# Top.net
KiCad netlist of a schematic drawn in Altium Designer
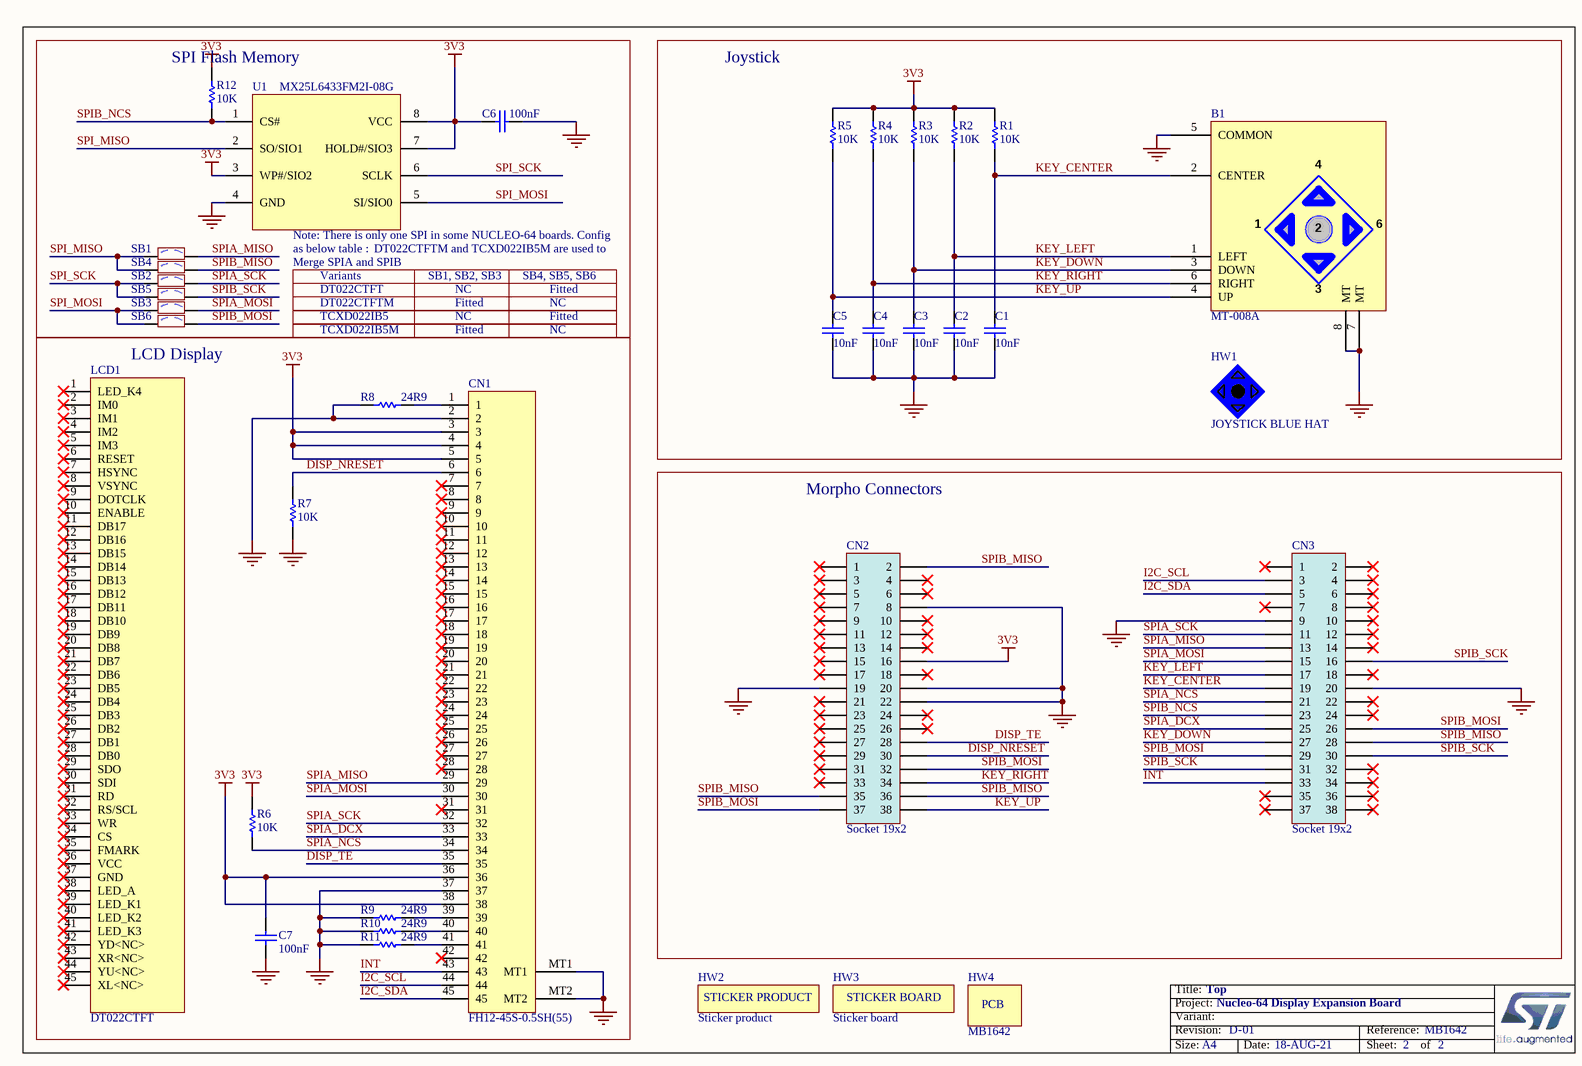
[diagram p0: Top.SchDoc]

(export (version "E")
  (design (tool "Eeschema 10.0.6"))
  (components
    (comp (ref "B1")
      (value "MT-008A")
      (footprint "SWI_XIEJIA_MT-008A_6P")
      (description "Joystick, 4 dir, 1 OK")
      (fields
        (field (name "INTERNAL_PART_NUMBER") "MCD-00132")
        (field (name "MANUFACTURER") "XIEJIA ELECTRONICS")
        (field (name "PROVIDED_BY") "SUBCO")
      )
      (libsource (lib "MCD_PARTS_database") (part "Joystick MT-008A_M"))
    )
    (comp (ref "C1")
      (value "10nF")
      (footprint "C0603")
      (description "Capacitor,10nF,100V,X7R,10%,0603")
      (fields
        (field (name "INTERNAL_PART_NUMBER") "MCD-01098")
        (field (name "MANUFACTURER_PART_NUMBER") "CC0603KRX7R0BB103")
        (field (name "PROVIDED_BY") "SUBCO")
      )
      (libsource (lib "MCD_PARTS_database") (part "Capacitor"))
    )
    (comp (ref "C2")
      (value "10nF")
      (footprint "C0603")
      (description "Capacitor,10nF,100V,X7R,10%,0603")
      (fields
        (field (name "INTERNAL_PART_NUMBER") "MCD-01098")
        (field (name "MANUFACTURER_PART_NUMBER") "CC0603KRX7R0BB103")
        (field (name "PROVIDED_BY") "SUBCO")
      )
      (libsource (lib "MCD_PARTS_database") (part "Capacitor"))
    )
    (comp (ref "C3")
      (value "10nF")
      (footprint "C0603")
      (description "Capacitor,10nF,100V,X7R,10%,0603")
      (fields
        (field (name "INTERNAL_PART_NUMBER") "MCD-01098")
        (field (name "MANUFACTURER_PART_NUMBER") "CC0603KRX7R0BB103")
        (field (name "PROVIDED_BY") "SUBCO")
      )
      (libsource (lib "MCD_PARTS_database") (part "Capacitor"))
    )
    (comp (ref "C4")
      (value "10nF")
      (footprint "C0603")
      (description "Capacitor,10nF,100V,X7R,10%,0603")
      (fields
        (field (name "INTERNAL_PART_NUMBER") "MCD-01098")
        (field (name "MANUFACTURER_PART_NUMBER") "CC0603KRX7R0BB103")
        (field (name "PROVIDED_BY") "SUBCO")
      )
      (libsource (lib "MCD_PARTS_database") (part "Capacitor"))
    )
    (comp (ref "C5")
      (value "10nF")
      (footprint "C0603")
      (description "Capacitor,10nF,100V,X7R,10%,0603")
      (fields
        (field (name "INTERNAL_PART_NUMBER") "MCD-01098")
        (field (name "MANUFACTURER_PART_NUMBER") "CC0603KRX7R0BB103")
        (field (name "PROVIDED_BY") "SUBCO")
      )
      (libsource (lib "MCD_PARTS_database") (part "Capacitor"))
    )
    (comp (ref "C6")
      (value "100nF")
      (footprint "C0603")
      (description "Capacitor, MLCC, 100nF, 16V, X7R, +/-10%, 0603, T=0,8mm")
      (fields (field (name "INTERNAL_PART_NUMBER") "MCD-00211") (field (name "MANUFACTURER") "YAGEO"))
      (libsource (lib "MCD_PARTS_database") (part "Capacitor"))
    )
    (comp (ref "C7")
      (value "100nF")
      (footprint "C0603")
      (description "Capacitor, MLCC, 100nF, 16V, X7R, +/-10%, 0603, T=0,8mm")
      (fields (field (name "INTERNAL_PART_NUMBER") "MCD-00211") (field (name "MANUFACTURER") "YAGEO"))
      (libsource (lib "MCD_PARTS_database") (part "Capacitor"))
    )
    (comp (ref "CN1")
      (value "FH12-45S-0.5SH(55)")
      (footprint "CON_HRS_FH12-45S-05SH")
      (description "45 pins P 0.5 surface mount connector")
      (fields
        (field (name "INTERNAL_PART_NUMBER") "MCD-01980")
        (field (name "MANUFACTURER") "HIROSE")
        (field (name "PROVIDED_BY") "SUBCO")
      )
      (libsource (lib "MCD_PARTS_database") (part "FH12-45S-0.5SH(55)"))
    )
    (comp (ref "CN2")
      (value "Socket 19x2")
      (footprint "CON_SAMTEC_SSW-119-01-X-D")
      (description "Socket, 19x2, 2.54mm, VR, TH, Height 8.51mm/2.64mm")
      (fields
        (field (name "INTERNAL_PART_NUMBER") "MCD-01845")
        (field (name "MANUFACTURER_PART_NUMBER") "SSW-119-01-x-D")
        (field (name "PROVIDED_BY") "SUBCO")
      )
      (libsource (lib "MCD_PARTS_database") (part "Socket 19x2"))
    )
    (comp (ref "CN3")
      (value "Socket 19x2")
      (footprint "CON_SAMTEC_SSW-119-01-X-D")
      (description "Socket, 19x2, 2.54mm, VR, TH, Height 8.51mm/2.64mm")
      (fields
        (field (name "INTERNAL_PART_NUMBER") "MCD-01845")
        (field (name "MANUFACTURER_PART_NUMBER") "SSW-119-01-x-D")
        (field (name "PROVIDED_BY") "SUBCO")
      )
      (libsource (lib "MCD_PARTS_database") (part "Socket 19x2"))
    )
    (comp (ref "HW1")
      (value "JOYSTICK BLUE HAT")
      (description "Joystick Blue Hat")
      (fields
        (field (name "INTERNAL_PART_NUMBER") "MCD-01337")
        (field (name "MANUFACTURER_PART_NUMBER") "PB-504")
        (field (name "PROVIDED_BY") "SUBCO")
      )
      (libsource (lib "MCD_PARTS_database") (part "JOYSTICK_BLUE_HAT"))
    )
    (comp (ref "HW2")
      (value "Sticker product")
      (footprint "STICKER_PRODUCT_25X5")
      (description "Sticker product 25x5 mm")
      (fields (field (name "INTERNAL_PART_NUMBER") "MCD-02189") (field (name "Comment") "STICKER_PRODUCT"))
      (libsource (lib "MCD_PARTS_database") (part "STICKER_PRODUCT"))
    )
    (comp (ref "HW3")
      (value "Sticker board")
      (footprint "STICKER_BOARD_25X5")
      (description "Sticker board 25x5 mm")
      (fields (field (name "INTERNAL_PART_NUMBER") "MCD-02190") (field (name "Comment") "STICKER_BOARD"))
      (libsource (lib "MCD_PARTS_database") (part "STICKER_BOARD"))
    )
    (comp (ref "HW4")
      (value "MB1642")
      (description "MB1642 PCB")
      (fields (field (name "INTERNAL_PART_NUMBER") "MCD-02495") (field (name "Comment") "PCB"))
      (libsource (lib "MCD_PARTS_database") (part "PCB"))
    )
    (comp (ref "LCD1")
      (value "DT022CTFT")
      (footprint "LCD_DISPLAYTECH_DT022CTFT_45P_P050")
      (description "240x320 2.2inch display")
      (fields
        (field (name "INTERNAL_PART_NUMBER") "MCD-01982")
        (field (name "MANUFACTURER") "DISPLAYTECH")
        (field (name "PROVIDED_BY") "SUBCO")
      )
      (libsource (lib "MCD_PARTS_database") (part "DT022CTFT"))
    )
    (comp (ref "R1")
      (value "10K")
      (footprint "R0603")
      (description "Resistor,10K,0603,1%,1/10W")
      (fields
        (field (name "INTERNAL_PART_NUMBER") "MCD-00220")
        (field (name "MANUFACTURER_PART_NUMBER") "RC0603FR-0710KL")
        (field (name "PROVIDED_BY") "SUBCO")
      )
      (libsource (lib "MCD_PARTS_database") (part "Resistor"))
    )
    (comp (ref "R2")
      (value "10K")
      (footprint "R0603")
      (description "Resistor,10K,0603,1%,1/10W")
      (fields
        (field (name "INTERNAL_PART_NUMBER") "MCD-00220")
        (field (name "MANUFACTURER_PART_NUMBER") "RC0603FR-0710KL")
        (field (name "PROVIDED_BY") "SUBCO")
      )
      (libsource (lib "MCD_PARTS_database") (part "Resistor"))
    )
    (comp (ref "R3")
      (value "10K")
      (footprint "R0603")
      (description "Resistor,10K,0603,1%,1/10W")
      (fields
        (field (name "INTERNAL_PART_NUMBER") "MCD-00220")
        (field (name "MANUFACTURER_PART_NUMBER") "RC0603FR-0710KL")
        (field (name "PROVIDED_BY") "SUBCO")
      )
      (libsource (lib "MCD_PARTS_database") (part "Resistor"))
    )
    (comp (ref "R4")
      (value "10K")
      (footprint "R0603")
      (description "Resistor,10K,0603,1%,1/10W")
      (fields
        (field (name "INTERNAL_PART_NUMBER") "MCD-00220")
        (field (name "MANUFACTURER_PART_NUMBER") "RC0603FR-0710KL")
        (field (name "PROVIDED_BY") "SUBCO")
      )
      (libsource (lib "MCD_PARTS_database") (part "Resistor"))
    )
    (comp (ref "R5")
      (value "10K")
      (footprint "R0603")
      (description "Resistor,10K,0603,1%,1/10W")
      (fields
        (field (name "INTERNAL_PART_NUMBER") "MCD-00220")
        (field (name "MANUFACTURER_PART_NUMBER") "RC0603FR-0710KL")
        (field (name "PROVIDED_BY") "SUBCO")
      )
      (libsource (lib "MCD_PARTS_database") (part "Resistor"))
    )
    (comp (ref "R6")
      (value "10K")
      (footprint "R0603")
      (description "Resistor,10K,0603,1%,1/10W")
      (fields
        (field (name "INTERNAL_PART_NUMBER") "MCD-00220")
        (field (name "MANUFACTURER_PART_NUMBER") "RC0603FR-0710KL")
        (field (name "PROVIDED_BY") "SUBCO")
      )
      (libsource (lib "MCD_PARTS_database") (part "Resistor"))
    )
    (comp (ref "R7")
      (value "10K")
      (footprint "R0603")
      (description "Resistor,10K,0603,1%,1/10W")
      (fields
        (field (name "INTERNAL_PART_NUMBER") "MCD-00220")
        (field (name "MANUFACTURER_PART_NUMBER") "RC0603FR-0710KL")
        (field (name "PROVIDED_BY") "SUBCO")
      )
      (libsource (lib "MCD_PARTS_database") (part "Resistor"))
    )
    (comp (ref "R8")
      (value "24R9")
      (footprint "R1206_H0P55")
      (description "Resistor, 24R9, 1206, +/-1%, 1/4W")
      (fields
        (field (name "INTERNAL_PART_NUMBER") "MCD-02611")
        (field (name "MANUFACTURER_PART_NUMBER") "RC1206FR-0724R9L")
      )
      (libsource (lib "MCD_PARTS_database") (part "Resistor"))
    )
    (comp (ref "R9")
      (value "24R9")
      (footprint "R1206_H0P55")
      (description "Resistor, 24R9, 1206, +/-1%, 1/4W")
      (fields
        (field (name "INTERNAL_PART_NUMBER") "MCD-02611")
        (field (name "MANUFACTURER_PART_NUMBER") "RC1206FR-0724R9L")
      )
      (libsource (lib "MCD_PARTS_database") (part "Resistor"))
    )
    (comp (ref "R10")
      (value "24R9")
      (footprint "R1206_H0P55")
      (description "Resistor, 24R9, 1206, +/-1%, 1/4W")
      (fields
        (field (name "INTERNAL_PART_NUMBER") "MCD-02611")
        (field (name "MANUFACTURER_PART_NUMBER") "RC1206FR-0724R9L")
      )
      (libsource (lib "MCD_PARTS_database") (part "Resistor"))
    )
    (comp (ref "R11")
      (value "24R9")
      (footprint "R1206_H0P55")
      (description "Resistor, 24R9, 1206, +/-1%, 1/4W")
      (fields
        (field (name "INTERNAL_PART_NUMBER") "MCD-02611")
        (field (name "MANUFACTURER_PART_NUMBER") "RC1206FR-0724R9L")
      )
      (libsource (lib "MCD_PARTS_database") (part "Resistor"))
    )
    (comp (ref "R12")
      (value "10K")
      (footprint "R0603")
      (description "Resistor,10K,0603,1%,1/10W")
      (fields
        (field (name "INTERNAL_PART_NUMBER") "MCD-00220")
        (field (name "MANUFACTURER_PART_NUMBER") "RC0603FR-0710KL")
        (field (name "PROVIDED_BY") "SUBCO")
      )
      (libsource (lib "MCD_PARTS_database") (part "Resistor"))
    )
    (comp (ref "SB1")
      (value "SB_OFF")
      (footprint "SOLDER-BRIDGE_R0603-0R")
      (description "Solder Bridge OFF")
      (fields (field (name "INTERNAL_PART_NUMBER") "MCD-00072") (field (name "MANUFACTURER") "YAGEO"))
      (libsource (lib "MCD_PARTS_database") (part "SB_OFF"))
    )
    (comp (ref "SB2")
      (value "SB_OFF")
      (footprint "SOLDER-BRIDGE_R0603-0R")
      (description "Solder Bridge OFF")
      (fields (field (name "INTERNAL_PART_NUMBER") "MCD-00072") (field (name "MANUFACTURER") "YAGEO"))
      (libsource (lib "MCD_PARTS_database") (part "SB_OFF"))
    )
    (comp (ref "SB3")
      (value "SB_OFF")
      (footprint "SOLDER-BRIDGE_R0603-0R")
      (description "Solder Bridge OFF")
      (fields (field (name "INTERNAL_PART_NUMBER") "MCD-00072") (field (name "MANUFACTURER") "YAGEO"))
      (libsource (lib "MCD_PARTS_database") (part "SB_OFF"))
    )
    (comp (ref "SB4")
      (value "SB_OFF")
      (footprint "SOLDER-BRIDGE_R0603-0R")
      (description "Solder Bridge OFF")
      (fields (field (name "INTERNAL_PART_NUMBER") "MCD-00072") (field (name "MANUFACTURER") "YAGEO"))
      (libsource (lib "MCD_PARTS_database") (part "SB_OFF"))
    )
    (comp (ref "SB5")
      (value "SB_OFF")
      (footprint "SOLDER-BRIDGE_R0603-0R")
      (description "Solder Bridge OFF")
      (fields (field (name "INTERNAL_PART_NUMBER") "MCD-00072") (field (name "MANUFACTURER") "YAGEO"))
      (libsource (lib "MCD_PARTS_database") (part "SB_OFF"))
    )
    (comp (ref "SB6")
      (value "SB_OFF")
      (footprint "SOLDER-BRIDGE_R0603-0R")
      (description "Solder Bridge OFF")
      (fields (field (name "INTERNAL_PART_NUMBER") "MCD-00072") (field (name "MANUFACTURER") "YAGEO"))
      (libsource (lib "MCD_PARTS_database") (part "SB_OFF"))
    )
    (comp (ref "U1")
      (value "MX25L6433FM2I-08G")
      (footprint "ICC_SOP8_5P23X5P28_P127")
      (fields
        (field (name "INTERNAL_PART_NUMBER") "MCD-01981")
        (field (name "MANUFACTURER") "MACRONIX")
        (field (name "PROVIDED_BY") "SUBCO")
      )
      (libsource (lib "MCD_PARTS_database") (part "MX25L6433FM2I-08G"))
    )
  )
  (nets
    (net (code "1") (name "/DISP_NRESET") (class "Default")
      (node (ref "CN1") (pin "6") (pinfunction "6_6") (pintype "passive"))
      (node (ref "CN2") (pin "30") (pinfunction "30_30") (pintype "passive"))
      (node (ref "R7") (pin "2") (pinfunction "2_2") (pintype "passive"))
    )
    (net (code "2") (name "/DISP_TE") (class "Default")
      (node (ref "CN1") (pin "35") (pinfunction "35_35") (pintype "passive"))
      (node (ref "CN2") (pin "28") (pinfunction "28_28") (pintype "passive"))
    )
    (net (code "3") (name "/I2C_SCL") (class "Default")
      (node (ref "CN1") (pin "44") (pinfunction "44_44") (pintype "passive"))
      (node (ref "CN3") (pin "3") (pinfunction "3_3") (pintype "passive"))
    )
    (net (code "4") (name "/I2C_SDA") (class "Default")
      (node (ref "CN1") (pin "45") (pinfunction "45_45") (pintype "passive"))
      (node (ref "CN3") (pin "5") (pinfunction "5_5") (pintype "passive"))
    )
    (net (code "5") (name "/INT") (class "Default")
      (node (ref "CN1") (pin "43") (pinfunction "43_43") (pintype "passive"))
      (node (ref "CN3") (pin "33") (pinfunction "33_33") (pintype "passive"))
    )
    (net (code "6") (name "/KEY_CENTER") (class "Default")
      (node (ref "B1") (pin "2") (pinfunction "CENTER_2") (pintype "passive"))
      (node (ref "C1") (pin "2") (pinfunction "2_2") (pintype "passive"))
      (node (ref "CN3") (pin "19") (pinfunction "19_19") (pintype "passive"))
      (node (ref "R1") (pin "2") (pinfunction "2_2") (pintype "passive"))
    )
    (net (code "7") (name "/KEY_DOWN") (class "Default")
      (node (ref "B1") (pin "3") (pinfunction "DOWN_3") (pintype "passive"))
      (node (ref "C3") (pin "2") (pinfunction "2_2") (pintype "passive"))
      (node (ref "CN3") (pin "27") (pinfunction "27_27") (pintype "passive"))
      (node (ref "R3") (pin "1") (pinfunction "1_1") (pintype "passive"))
    )
    (net (code "8") (name "/KEY_LEFT") (class "Default")
      (node (ref "B1") (pin "1") (pinfunction "LEFT_1") (pintype "passive"))
      (node (ref "C2") (pin "2") (pinfunction "2_2") (pintype "passive"))
      (node (ref "CN3") (pin "17") (pinfunction "17_17") (pintype "passive"))
      (node (ref "R2") (pin "1") (pinfunction "1_1") (pintype "passive"))
    )
    (net (code "9") (name "/KEY_RIGHT") (class "Default")
      (node (ref "B1") (pin "6") (pinfunction "RIGHT_6") (pintype "passive"))
      (node (ref "C4") (pin "2") (pinfunction "2_2") (pintype "passive"))
      (node (ref "CN2") (pin "34") (pinfunction "34_34") (pintype "passive"))
      (node (ref "R4") (pin "1") (pinfunction "1_1") (pintype "passive"))
    )
    (net (code "10") (name "/KEY_UP") (class "Default")
      (node (ref "B1") (pin "4") (pinfunction "UP_4") (pintype "passive"))
      (node (ref "C5") (pin "2") (pinfunction "2_2") (pintype "passive"))
      (node (ref "CN2") (pin "38") (pinfunction "38_38") (pintype "passive"))
      (node (ref "R5") (pin "1") (pinfunction "1_1") (pintype "passive"))
    )
    (net (code "11") (name "/SPIA_DCX") (class "Default")
      (node (ref "CN1") (pin "33") (pinfunction "33_33") (pintype "passive"))
      (node (ref "CN3") (pin "25") (pinfunction "25_25") (pintype "passive"))
    )
    (net (code "12") (name "/SPIA_MISO") (class "Default")
      (node (ref "CN1") (pin "29") (pinfunction "29_29") (pintype "passive"))
      (node (ref "CN3") (pin "13") (pinfunction "13_13") (pintype "passive"))
      (node (ref "SB1") (pin "2") (pinfunction "2_2") (pintype "passive"))
    )
    (net (code "13") (name "/SPIA_MOSI") (class "Default")
      (node (ref "CN1") (pin "30") (pinfunction "30_30") (pintype "passive"))
      (node (ref "CN3") (pin "15") (pinfunction "15_15") (pintype "passive"))
      (node (ref "SB3") (pin "2") (pinfunction "2_2") (pintype "passive"))
    )
    (net (code "14") (name "/SPIA_NCS") (class "Default")
      (node (ref "CN1") (pin "34") (pinfunction "34_34") (pintype "passive"))
      (node (ref "CN3") (pin "21") (pinfunction "21_21") (pintype "passive"))
      (node (ref "R6") (pin "1") (pinfunction "1_1") (pintype "passive"))
    )
    (net (code "15") (name "/SPIA_SCK") (class "Default")
      (node (ref "CN1") (pin "32") (pinfunction "32_32") (pintype "passive"))
      (node (ref "CN3") (pin "11") (pinfunction "11_11") (pintype "passive"))
      (node (ref "SB2") (pin "2") (pinfunction "2_2") (pintype "passive"))
    )
    (net (code "16") (name "/SPIB_MISO") (class "Default")
      (node (ref "CN2") (pin "2") (pinfunction "2_2") (pintype "passive"))
      (node (ref "CN2") (pin "35") (pinfunction "35_35") (pintype "passive"))
      (node (ref "CN2") (pin "36") (pinfunction "36_36") (pintype "passive"))
      (node (ref "CN3") (pin "28") (pinfunction "28_28") (pintype "passive"))
      (node (ref "SB4") (pin "2") (pinfunction "2_2") (pintype "passive"))
    )
    (net (code "17") (name "/SPIB_MOSI") (class "Default")
      (node (ref "CN2") (pin "32") (pinfunction "32_32") (pintype "passive"))
      (node (ref "CN2") (pin "37") (pinfunction "37_37") (pintype "passive"))
      (node (ref "CN3") (pin "26") (pinfunction "26_26") (pintype "passive"))
      (node (ref "CN3") (pin "29") (pinfunction "29_29") (pintype "passive"))
      (node (ref "SB6") (pin "2") (pinfunction "2_2") (pintype "passive"))
    )
    (net (code "18") (name "/SPIB_NCS") (class "Default")
      (node (ref "CN3") (pin "23") (pinfunction "23_23") (pintype "passive"))
      (node (ref "R12") (pin "2") (pinfunction "2_2") (pintype "passive"))
      (node (ref "U1") (pin "1") (pinfunction "CS#_1") (pintype "passive"))
    )
    (net (code "19") (name "/SPIB_SCK") (class "Default")
      (node (ref "CN3") (pin "16") (pinfunction "16_16") (pintype "passive"))
      (node (ref "CN3") (pin "30") (pinfunction "30_30") (pintype "passive"))
      (node (ref "CN3") (pin "31") (pinfunction "31_31") (pintype "passive"))
      (node (ref "SB5") (pin "2") (pinfunction "2_2") (pintype "passive"))
    )
    (net (code "20") (name "/SPI_MISO") (class "Default")
      (node (ref "SB1") (pin "1") (pinfunction "1_1") (pintype "passive"))
      (node (ref "SB4") (pin "1") (pinfunction "1_1") (pintype "passive"))
      (node (ref "U1") (pin "2") (pinfunction "SO/SIO1_2") (pintype "passive"))
    )
    (net (code "21") (name "/SPI_MOSI") (class "Default")
      (node (ref "SB3") (pin "1") (pinfunction "1_1") (pintype "passive"))
      (node (ref "SB6") (pin "1") (pinfunction "1_1") (pintype "passive"))
      (node (ref "U1") (pin "5") (pinfunction "SI/SIO0_5") (pintype "passive"))
    )
    (net (code "22") (name "/SPI_SCK") (class "Default")
      (node (ref "SB2") (pin "1") (pinfunction "1_1") (pintype "passive"))
      (node (ref "SB5") (pin "1") (pinfunction "1_1") (pintype "passive"))
      (node (ref "U1") (pin "6") (pinfunction "SCLK_6") (pintype "passive"))
    )
    (net (code "23") (name "3V3") (class "Default")
      (node (ref "C6") (pin "1") (pinfunction "1_1") (pintype "passive"))
      (node (ref "C7") (pin "2") (pinfunction "2_2") (pintype "passive"))
      (node (ref "CN1") (pin "3") (pinfunction "3_3") (pintype "passive"))
      (node (ref "CN1") (pin "36") (pinfunction "36_36") (pintype "passive"))
      (node (ref "CN1") (pin "38") (pinfunction "38_38") (pintype "passive"))
      (node (ref "CN1") (pin "4") (pinfunction "4_4") (pintype "passive"))
      (node (ref "CN1") (pin "5") (pinfunction "5_5") (pintype "passive"))
      (node (ref "CN2") (pin "16") (pinfunction "16_16") (pintype "passive"))
      (node (ref "R1") (pin "1") (pinfunction "1_1") (pintype "passive"))
      (node (ref "R12") (pin "1") (pinfunction "1_1") (pintype "passive"))
      (node (ref "R2") (pin "2") (pinfunction "2_2") (pintype "passive"))
      (node (ref "R3") (pin "2") (pinfunction "2_2") (pintype "passive"))
      (node (ref "R4") (pin "2") (pinfunction "2_2") (pintype "passive"))
      (node (ref "R5") (pin "2") (pinfunction "2_2") (pintype "passive"))
      (node (ref "R6") (pin "2") (pinfunction "2_2") (pintype "passive"))
      (node (ref "U1") (pin "3") (pinfunction "WP#/SIO2_3") (pintype "passive"))
      (node (ref "U1") (pin "7") (pinfunction "HOLD#/SIO3_7") (pintype "passive"))
      (node (ref "U1") (pin "8") (pinfunction "VCC_8") (pintype "passive"))
    )
    (net (code "24") (name "GND") (class "Default")
      (node (ref "B1") (pin "5") (pinfunction "COMMON_5") (pintype "passive"))
      (node (ref "B1") (pin "7") (pinfunction "MT_7") (pintype "passive"))
      (node (ref "B1") (pin "8") (pinfunction "MT_8") (pintype "passive"))
      (node (ref "C1") (pin "1") (pinfunction "1_1") (pintype "passive"))
      (node (ref "C2") (pin "1") (pinfunction "1_1") (pintype "passive"))
      (node (ref "C3") (pin "1") (pinfunction "1_1") (pintype "passive"))
      (node (ref "C4") (pin "1") (pinfunction "1_1") (pintype "passive"))
      (node (ref "C5") (pin "1") (pinfunction "1_1") (pintype "passive"))
      (node (ref "C6") (pin "2") (pinfunction "2_2") (pintype "passive"))
      (node (ref "C7") (pin "1") (pinfunction "1_1") (pintype "passive"))
      (node (ref "CN1") (pin "2") (pinfunction "2_2") (pintype "passive"))
      (node (ref "CN1") (pin "37") (pinfunction "37_37") (pintype "passive"))
      (node (ref "CN1") (pin "MT1") (pinfunction "MT1_MT1") (pintype "passive"))
      (node (ref "CN1") (pin "MT2") (pinfunction "MT2_MT2") (pintype "passive"))
      (node (ref "CN2") (pin "19") (pinfunction "19_19") (pintype "passive"))
      (node (ref "CN2") (pin "20") (pinfunction "20_20") (pintype "passive"))
      (node (ref "CN2") (pin "22") (pinfunction "22_22") (pintype "passive"))
      (node (ref "CN2") (pin "8") (pinfunction "8_8") (pintype "passive"))
      (node (ref "CN3") (pin "20") (pinfunction "20_20") (pintype "passive"))
      (node (ref "CN3") (pin "9") (pinfunction "9_9") (pintype "passive"))
      (node (ref "R10") (pin "1") (pinfunction "1_1") (pintype "passive"))
      (node (ref "R11") (pin "1") (pinfunction "1_1") (pintype "passive"))
      (node (ref "R7") (pin "1") (pinfunction "1_1") (pintype "passive"))
      (node (ref "R8") (pin "1") (pinfunction "1_1") (pintype "passive"))
      (node (ref "R9") (pin "1") (pinfunction "1_1") (pintype "passive"))
      (node (ref "U1") (pin "4") (pinfunction "GND_4") (pintype "passive"))
    )
    (net (code "25") (name "Net-(CN1-Pad1)") (class "Default")
      (node (ref "CN1") (pin "1") (pinfunction "1_1") (pintype "passive"))
      (node (ref "R8") (pin "2") (pinfunction "2_2") (pintype "passive"))
    )
    (net (code "26") (name "Net-(CN1-Pad39)") (class "Default")
      (node (ref "CN1") (pin "39") (pinfunction "39_39") (pintype "passive"))
      (node (ref "R9") (pin "2") (pinfunction "2_2") (pintype "passive"))
    )
    (net (code "27") (name "Net-(CN1-Pad40)") (class "Default")
      (node (ref "CN1") (pin "40") (pinfunction "40_40") (pintype "passive"))
      (node (ref "R10") (pin "2") (pinfunction "2_2") (pintype "passive"))
    )
    (net (code "28") (name "Net-(CN1-Pad41)") (class "Default")
      (node (ref "CN1") (pin "41") (pinfunction "41_41") (pintype "passive"))
      (node (ref "R11") (pin "2") (pinfunction "2_2") (pintype "passive"))
    )
    (net (code "29") (name "unconnected-(CN1-Pad7)") (class "Default")
      (node (ref "CN1") (pin "7") (pinfunction "7_7") (pintype "passive+no_connect"))
    )
    (net (code "30") (name "unconnected-(CN1-Pad8)") (class "Default")
      (node (ref "CN1") (pin "8") (pinfunction "8_8") (pintype "passive+no_connect"))
    )
    (net (code "31") (name "unconnected-(CN1-Pad9)") (class "Default")
      (node (ref "CN1") (pin "9") (pinfunction "9_9") (pintype "passive+no_connect"))
    )
    (net (code "32") (name "unconnected-(CN1-Pad10)") (class "Default")
      (node (ref "CN1") (pin "10") (pinfunction "10_10") (pintype "passive+no_connect"))
    )
    (net (code "33") (name "unconnected-(CN1-Pad11)") (class "Default")
      (node (ref "CN1") (pin "11") (pinfunction "11_11") (pintype "passive+no_connect"))
    )
    (net (code "34") (name "unconnected-(CN1-Pad12)") (class "Default")
      (node (ref "CN1") (pin "12") (pinfunction "12_12") (pintype "passive+no_connect"))
    )
    (net (code "35") (name "unconnected-(CN1-Pad13)") (class "Default")
      (node (ref "CN1") (pin "13") (pinfunction "13_13") (pintype "passive+no_connect"))
    )
    (net (code "36") (name "unconnected-(CN1-Pad14)") (class "Default")
      (node (ref "CN1") (pin "14") (pinfunction "14_14") (pintype "passive+no_connect"))
    )
    (net (code "37") (name "unconnected-(CN1-Pad15)") (class "Default")
      (node (ref "CN1") (pin "15") (pinfunction "15_15") (pintype "passive+no_connect"))
    )
    (net (code "38") (name "unconnected-(CN1-Pad16)") (class "Default")
      (node (ref "CN1") (pin "16") (pinfunction "16_16") (pintype "passive+no_connect"))
    )
    (net (code "39") (name "unconnected-(CN1-Pad17)") (class "Default")
      (node (ref "CN1") (pin "17") (pinfunction "17_17") (pintype "passive+no_connect"))
    )
    (net (code "40") (name "unconnected-(CN1-Pad18)") (class "Default")
      (node (ref "CN1") (pin "18") (pinfunction "18_18") (pintype "passive+no_connect"))
    )
    (net (code "41") (name "unconnected-(CN1-Pad19)") (class "Default")
      (node (ref "CN1") (pin "19") (pinfunction "19_19") (pintype "passive+no_connect"))
    )
    (net (code "42") (name "unconnected-(CN1-Pad20)") (class "Default")
      (node (ref "CN1") (pin "20") (pinfunction "20_20") (pintype "passive+no_connect"))
    )
    (net (code "43") (name "unconnected-(CN1-Pad21)") (class "Default")
      (node (ref "CN1") (pin "21") (pinfunction "21_21") (pintype "passive+no_connect"))
    )
    (net (code "44") (name "unconnected-(CN1-Pad22)") (class "Default")
      (node (ref "CN1") (pin "22") (pinfunction "22_22") (pintype "passive+no_connect"))
    )
    (net (code "45") (name "unconnected-(CN1-Pad23)") (class "Default")
      (node (ref "CN1") (pin "23") (pinfunction "23_23") (pintype "passive+no_connect"))
    )
    (net (code "46") (name "unconnected-(CN1-Pad24)") (class "Default")
      (node (ref "CN1") (pin "24") (pinfunction "24_24") (pintype "passive+no_connect"))
    )
    (net (code "47") (name "unconnected-(CN1-Pad25)") (class "Default")
      (node (ref "CN1") (pin "25") (pinfunction "25_25") (pintype "passive+no_connect"))
    )
    (net (code "48") (name "unconnected-(CN1-Pad26)") (class "Default")
      (node (ref "CN1") (pin "26") (pinfunction "26_26") (pintype "passive+no_connect"))
    )
    (net (code "49") (name "unconnected-(CN1-Pad27)") (class "Default")
      (node (ref "CN1") (pin "27") (pinfunction "27_27") (pintype "passive+no_connect"))
    )
    (net (code "50") (name "unconnected-(CN1-Pad28)") (class "Default")
      (node (ref "CN1") (pin "28") (pinfunction "28_28") (pintype "passive+no_connect"))
    )
    (net (code "51") (name "unconnected-(CN1-Pad31)") (class "Default")
      (node (ref "CN1") (pin "31") (pinfunction "31_31") (pintype "passive+no_connect"))
    )
    (net (code "52") (name "unconnected-(CN1-Pad42)") (class "Default")
      (node (ref "CN1") (pin "42") (pinfunction "42_42") (pintype "passive+no_connect"))
    )
    (net (code "53") (name "unconnected-(CN2-Pad1)") (class "Default")
      (node (ref "CN2") (pin "1") (pinfunction "1_1") (pintype "passive+no_connect"))
    )
    (net (code "54") (name "unconnected-(CN2-Pad3)") (class "Default")
      (node (ref "CN2") (pin "3") (pinfunction "3_3") (pintype "passive+no_connect"))
    )
    (net (code "55") (name "unconnected-(CN2-Pad4)") (class "Default")
      (node (ref "CN2") (pin "4") (pinfunction "4_4") (pintype "passive+no_connect"))
    )
    (net (code "56") (name "unconnected-(CN2-Pad5)") (class "Default")
      (node (ref "CN2") (pin "5") (pinfunction "5_5") (pintype "passive+no_connect"))
    )
    (net (code "57") (name "unconnected-(CN2-Pad6)") (class "Default")
      (node (ref "CN2") (pin "6") (pinfunction "6_6") (pintype "passive+no_connect"))
    )
    (net (code "58") (name "unconnected-(CN2-Pad7)") (class "Default")
      (node (ref "CN2") (pin "7") (pinfunction "7_7") (pintype "passive+no_connect"))
    )
    (net (code "59") (name "unconnected-(CN2-Pad9)") (class "Default")
      (node (ref "CN2") (pin "9") (pinfunction "9_9") (pintype "passive+no_connect"))
    )
    (net (code "60") (name "unconnected-(CN2-Pad10)") (class "Default")
      (node (ref "CN2") (pin "10") (pinfunction "10_10") (pintype "passive+no_connect"))
    )
    (net (code "61") (name "unconnected-(CN2-Pad11)") (class "Default")
      (node (ref "CN2") (pin "11") (pinfunction "11_11") (pintype "passive+no_connect"))
    )
    (net (code "62") (name "unconnected-(CN2-Pad12)") (class "Default")
      (node (ref "CN2") (pin "12") (pinfunction "12_12") (pintype "passive+no_connect"))
    )
    (net (code "63") (name "unconnected-(CN2-Pad13)") (class "Default")
      (node (ref "CN2") (pin "13") (pinfunction "13_13") (pintype "passive+no_connect"))
    )
    (net (code "64") (name "unconnected-(CN2-Pad14)") (class "Default")
      (node (ref "CN2") (pin "14") (pinfunction "14_14") (pintype "passive+no_connect"))
    )
    (net (code "65") (name "unconnected-(CN2-Pad15)") (class "Default")
      (node (ref "CN2") (pin "15") (pinfunction "15_15") (pintype "passive+no_connect"))
    )
    (net (code "66") (name "unconnected-(CN2-Pad17)") (class "Default")
      (node (ref "CN2") (pin "17") (pinfunction "17_17") (pintype "passive+no_connect"))
    )
    (net (code "67") (name "unconnected-(CN2-Pad18)") (class "Default")
      (node (ref "CN2") (pin "18") (pinfunction "18_18") (pintype "passive+no_connect"))
    )
    (net (code "68") (name "unconnected-(CN2-Pad21)") (class "Default")
      (node (ref "CN2") (pin "21") (pinfunction "21_21") (pintype "passive+no_connect"))
    )
    (net (code "69") (name "unconnected-(CN2-Pad23)") (class "Default")
      (node (ref "CN2") (pin "23") (pinfunction "23_23") (pintype "passive+no_connect"))
    )
    (net (code "70") (name "unconnected-(CN2-Pad24)") (class "Default")
      (node (ref "CN2") (pin "24") (pinfunction "24_24") (pintype "passive+no_connect"))
    )
    (net (code "71") (name "unconnected-(CN2-Pad25)") (class "Default")
      (node (ref "CN2") (pin "25") (pinfunction "25_25") (pintype "passive+no_connect"))
    )
    (net (code "72") (name "unconnected-(CN2-Pad26)") (class "Default")
      (node (ref "CN2") (pin "26") (pinfunction "26_26") (pintype "passive+no_connect"))
    )
    (net (code "73") (name "unconnected-(CN2-Pad27)") (class "Default")
      (node (ref "CN2") (pin "27") (pinfunction "27_27") (pintype "passive+no_connect"))
    )
    (net (code "74") (name "unconnected-(CN2-Pad29)") (class "Default")
      (node (ref "CN2") (pin "29") (pinfunction "29_29") (pintype "passive+no_connect"))
    )
    (net (code "75") (name "unconnected-(CN2-Pad31)") (class "Default")
      (node (ref "CN2") (pin "31") (pinfunction "31_31") (pintype "passive+no_connect"))
    )
    (net (code "76") (name "unconnected-(CN2-Pad33)") (class "Default")
      (node (ref "CN2") (pin "33") (pinfunction "33_33") (pintype "passive+no_connect"))
    )
    (net (code "77") (name "unconnected-(CN3-Pad1)") (class "Default")
      (node (ref "CN3") (pin "1") (pinfunction "1_1") (pintype "passive+no_connect"))
    )
    (net (code "78") (name "unconnected-(CN3-Pad2)") (class "Default")
      (node (ref "CN3") (pin "2") (pinfunction "2_2") (pintype "passive+no_connect"))
    )
    (net (code "79") (name "unconnected-(CN3-Pad4)") (class "Default")
      (node (ref "CN3") (pin "4") (pinfunction "4_4") (pintype "passive+no_connect"))
    )
    (net (code "80") (name "unconnected-(CN3-Pad6)") (class "Default")
      (node (ref "CN3") (pin "6") (pinfunction "6_6") (pintype "passive+no_connect"))
    )
    (net (code "81") (name "unconnected-(CN3-Pad7)") (class "Default")
      (node (ref "CN3") (pin "7") (pinfunction "7_7") (pintype "passive+no_connect"))
    )
    (net (code "82") (name "unconnected-(CN3-Pad8)") (class "Default")
      (node (ref "CN3") (pin "8") (pinfunction "8_8") (pintype "passive+no_connect"))
    )
    (net (code "83") (name "unconnected-(CN3-Pad10)") (class "Default")
      (node (ref "CN3") (pin "10") (pinfunction "10_10") (pintype "passive+no_connect"))
    )
    (net (code "84") (name "unconnected-(CN3-Pad12)") (class "Default")
      (node (ref "CN3") (pin "12") (pinfunction "12_12") (pintype "passive+no_connect"))
    )
    (net (code "85") (name "unconnected-(CN3-Pad14)") (class "Default")
      (node (ref "CN3") (pin "14") (pinfunction "14_14") (pintype "passive+no_connect"))
    )
    (net (code "86") (name "unconnected-(CN3-Pad18)") (class "Default")
      (node (ref "CN3") (pin "18") (pinfunction "18_18") (pintype "passive+no_connect"))
    )
    (net (code "87") (name "unconnected-(CN3-Pad22)") (class "Default")
      (node (ref "CN3") (pin "22") (pinfunction "22_22") (pintype "passive+no_connect"))
    )
    (net (code "88") (name "unconnected-(CN3-Pad24)") (class "Default")
      (node (ref "CN3") (pin "24") (pinfunction "24_24") (pintype "passive+no_connect"))
    )
    (net (code "89") (name "unconnected-(CN3-Pad32)") (class "Default")
      (node (ref "CN3") (pin "32") (pinfunction "32_32") (pintype "passive+no_connect"))
    )
    (net (code "90") (name "unconnected-(CN3-Pad34)") (class "Default")
      (node (ref "CN3") (pin "34") (pinfunction "34_34") (pintype "passive+no_connect"))
    )
    (net (code "91") (name "unconnected-(CN3-Pad35)") (class "Default")
      (node (ref "CN3") (pin "35") (pinfunction "35_35") (pintype "passive+no_connect"))
    )
    (net (code "92") (name "unconnected-(CN3-Pad36)") (class "Default")
      (node (ref "CN3") (pin "36") (pinfunction "36_36") (pintype "passive+no_connect"))
    )
    (net (code "93") (name "unconnected-(CN3-Pad37)") (class "Default")
      (node (ref "CN3") (pin "37") (pinfunction "37_37") (pintype "passive+no_connect"))
    )
    (net (code "94") (name "unconnected-(CN3-Pad38)") (class "Default")
      (node (ref "CN3") (pin "38") (pinfunction "38_38") (pintype "passive+no_connect"))
    )
    (net (code "95") (name "unconnected-(LCD1-CS-Pad34)") (class "Default")
      (node (ref "LCD1") (pin "34") (pinfunction "CS_34") (pintype "passive+no_connect"))
    )
    (net (code "96") (name "unconnected-(LCD1-DB0-Pad28)") (class "Default")
      (node (ref "LCD1") (pin "28") (pinfunction "DB0_28") (pintype "passive+no_connect"))
    )
    (net (code "97") (name "unconnected-(LCD1-DB1-Pad27)") (class "Default")
      (node (ref "LCD1") (pin "27") (pinfunction "DB1_27") (pintype "passive+no_connect"))
    )
    (net (code "98") (name "unconnected-(LCD1-DB2-Pad26)") (class "Default")
      (node (ref "LCD1") (pin "26") (pinfunction "DB2_26") (pintype "passive+no_connect"))
    )
    (net (code "99") (name "unconnected-(LCD1-DB3-Pad25)") (class "Default")
      (node (ref "LCD1") (pin "25") (pinfunction "DB3_25") (pintype "passive+no_connect"))
    )
    (net (code "100") (name "unconnected-(LCD1-DB4-Pad24)") (class "Default")
      (node (ref "LCD1") (pin "24") (pinfunction "DB4_24") (pintype "passive+no_connect"))
    )
    (net (code "101") (name "unconnected-(LCD1-DB5-Pad23)") (class "Default")
      (node (ref "LCD1") (pin "23") (pinfunction "DB5_23") (pintype "passive+no_connect"))
    )
    (net (code "102") (name "unconnected-(LCD1-DB6-Pad22)") (class "Default")
      (node (ref "LCD1") (pin "22") (pinfunction "DB6_22") (pintype "passive+no_connect"))
    )
    (net (code "103") (name "unconnected-(LCD1-DB7-Pad21)") (class "Default")
      (node (ref "LCD1") (pin "21") (pinfunction "DB7_21") (pintype "passive+no_connect"))
    )
    (net (code "104") (name "unconnected-(LCD1-DB8-Pad20)") (class "Default")
      (node (ref "LCD1") (pin "20") (pinfunction "DB8_20") (pintype "passive+no_connect"))
    )
    (net (code "105") (name "unconnected-(LCD1-DB9-Pad19)") (class "Default")
      (node (ref "LCD1") (pin "19") (pinfunction "DB9_19") (pintype "passive+no_connect"))
    )
    (net (code "106") (name "unconnected-(LCD1-DB10-Pad18)") (class "Default")
      (node (ref "LCD1") (pin "18") (pinfunction "DB10_18") (pintype "passive+no_connect"))
    )
    (net (code "107") (name "unconnected-(LCD1-DB11-Pad17)") (class "Default")
      (node (ref "LCD1") (pin "17") (pinfunction "DB11_17") (pintype "passive+no_connect"))
    )
    (net (code "108") (name "unconnected-(LCD1-DB12-Pad16)") (class "Default")
      (node (ref "LCD1") (pin "16") (pinfunction "DB12_16") (pintype "passive+no_connect"))
    )
    (net (code "109") (name "unconnected-(LCD1-DB13-Pad15)") (class "Default")
      (node (ref "LCD1") (pin "15") (pinfunction "DB13_15") (pintype "passive+no_connect"))
    )
    (net (code "110") (name "unconnected-(LCD1-DB14-Pad14)") (class "Default")
      (node (ref "LCD1") (pin "14") (pinfunction "DB14_14") (pintype "passive+no_connect"))
    )
    (net (code "111") (name "unconnected-(LCD1-DB15-Pad13)") (class "Default")
      (node (ref "LCD1") (pin "13") (pinfunction "DB15_13") (pintype "passive+no_connect"))
    )
    (net (code "112") (name "unconnected-(LCD1-DB16-Pad12)") (class "Default")
      (node (ref "LCD1") (pin "12") (pinfunction "DB16_12") (pintype "passive+no_connect"))
    )
    (net (code "113") (name "unconnected-(LCD1-DB17-Pad11)") (class "Default")
      (node (ref "LCD1") (pin "11") (pinfunction "DB17_11") (pintype "passive+no_connect"))
    )
    (net (code "114") (name "unconnected-(LCD1-DOTCLK-Pad9)") (class "Default")
      (node (ref "LCD1") (pin "9") (pinfunction "DOTCLK_9") (pintype "passive+no_connect"))
    )
    (net (code "115") (name "unconnected-(LCD1-ENABLE-Pad10)") (class "Default")
      (node (ref "LCD1") (pin "10") (pinfunction "ENABLE_10") (pintype "passive+no_connect"))
    )
    (net (code "116") (name "unconnected-(LCD1-FMARK-Pad35)") (class "Default")
      (node (ref "LCD1") (pin "35") (pinfunction "FMARK_35") (pintype "passive+no_connect"))
    )
    (net (code "117") (name "unconnected-(LCD1-GND-Pad37)") (class "Default")
      (node (ref "LCD1") (pin "37") (pinfunction "GND_37") (pintype "passive+no_connect"))
    )
    (net (code "118") (name "unconnected-(LCD1-HSYNC-Pad7)") (class "Default")
      (node (ref "LCD1") (pin "7") (pinfunction "HSYNC_7") (pintype "passive+no_connect"))
    )
    (net (code "119") (name "unconnected-(LCD1-IM0-Pad2)") (class "Default")
      (node (ref "LCD1") (pin "2") (pinfunction "IM0_2") (pintype "passive+no_connect"))
    )
    (net (code "120") (name "unconnected-(LCD1-IM1-Pad3)") (class "Default")
      (node (ref "LCD1") (pin "3") (pinfunction "IM1_3") (pintype "passive+no_connect"))
    )
    (net (code "121") (name "unconnected-(LCD1-IM2-Pad4)") (class "Default")
      (node (ref "LCD1") (pin "4") (pinfunction "IM2_4") (pintype "passive+no_connect"))
    )
    (net (code "122") (name "unconnected-(LCD1-IM3-Pad5)") (class "Default")
      (node (ref "LCD1") (pin "5") (pinfunction "IM3_5") (pintype "passive+no_connect"))
    )
    (net (code "123") (name "unconnected-(LCD1-LED_A-Pad38)") (class "Default")
      (node (ref "LCD1") (pin "38") (pinfunction "LED_A_38") (pintype "passive+no_connect"))
    )
    (net (code "124") (name "unconnected-(LCD1-LED_K1-Pad39)") (class "Default")
      (node (ref "LCD1") (pin "39") (pinfunction "LED_K1_39") (pintype "passive+no_connect"))
    )
    (net (code "125") (name "unconnected-(LCD1-LED_K2-Pad40)") (class "Default")
      (node (ref "LCD1") (pin "40") (pinfunction "LED_K2_40") (pintype "passive+no_connect"))
    )
    (net (code "126") (name "unconnected-(LCD1-LED_K3-Pad41)") (class "Default")
      (node (ref "LCD1") (pin "41") (pinfunction "LED_K3_41") (pintype "passive+no_connect"))
    )
    (net (code "127") (name "unconnected-(LCD1-LED_K4-Pad1)") (class "Default")
      (node (ref "LCD1") (pin "1") (pinfunction "LED_K4_1") (pintype "passive+no_connect"))
    )
    (net (code "128") (name "unconnected-(LCD1-RD-Pad31)") (class "Default")
      (node (ref "LCD1") (pin "31") (pinfunction "RD_31") (pintype "passive+no_connect"))
    )
    (net (code "129") (name "unconnected-(LCD1-RESET-Pad6)") (class "Default")
      (node (ref "LCD1") (pin "6") (pinfunction "RESET_6") (pintype "passive+no_connect"))
    )
    (net (code "130") (name "unconnected-(LCD1-RS{slash}SCL-Pad32)") (class "Default")
      (node (ref "LCD1") (pin "32") (pinfunction "RS/SCL_32") (pintype "passive+no_connect"))
    )
    (net (code "131") (name "unconnected-(LCD1-SDI-Pad30)") (class "Default")
      (node (ref "LCD1") (pin "30") (pinfunction "SDI_30") (pintype "passive+no_connect"))
    )
    (net (code "132") (name "unconnected-(LCD1-SDO-Pad29)") (class "Default")
      (node (ref "LCD1") (pin "29") (pinfunction "SDO_29") (pintype "passive+no_connect"))
    )
    (net (code "133") (name "unconnected-(LCD1-VCC-Pad36)") (class "Default")
      (node (ref "LCD1") (pin "36") (pinfunction "VCC_36") (pintype "passive+no_connect"))
    )
    (net (code "134") (name "unconnected-(LCD1-VSYNC-Pad8)") (class "Default")
      (node (ref "LCD1") (pin "8") (pinfunction "VSYNC_8") (pintype "passive+no_connect"))
    )
    (net (code "135") (name "unconnected-(LCD1-WR-Pad33)") (class "Default")
      (node (ref "LCD1") (pin "33") (pinfunction "WR_33") (pintype "passive+no_connect"))
    )
    (net (code "136") (name "unconnected-(LCD1-XL<NC>-Pad45)") (class "Default")
      (node (ref "LCD1") (pin "45") (pinfunction "XL<NC>_45") (pintype "passive+no_connect"))
    )
    (net (code "137") (name "unconnected-(LCD1-XR<NC>-Pad43)") (class "Default")
      (node (ref "LCD1") (pin "43") (pinfunction "XR<NC>_43") (pintype "passive+no_connect"))
    )
    (net (code "138") (name "unconnected-(LCD1-YD<NC>-Pad42)") (class "Default")
      (node (ref "LCD1") (pin "42") (pinfunction "YD<NC>_42") (pintype "passive+no_connect"))
    )
    (net (code "139") (name "unconnected-(LCD1-YU<NC>-Pad44)") (class "Default")
      (node (ref "LCD1") (pin "44") (pinfunction "YU<NC>_44") (pintype "passive+no_connect"))
    )
  )
)
